# T4p0_cutout.net
KiCad netlist of a schematic drawn in EAGLE
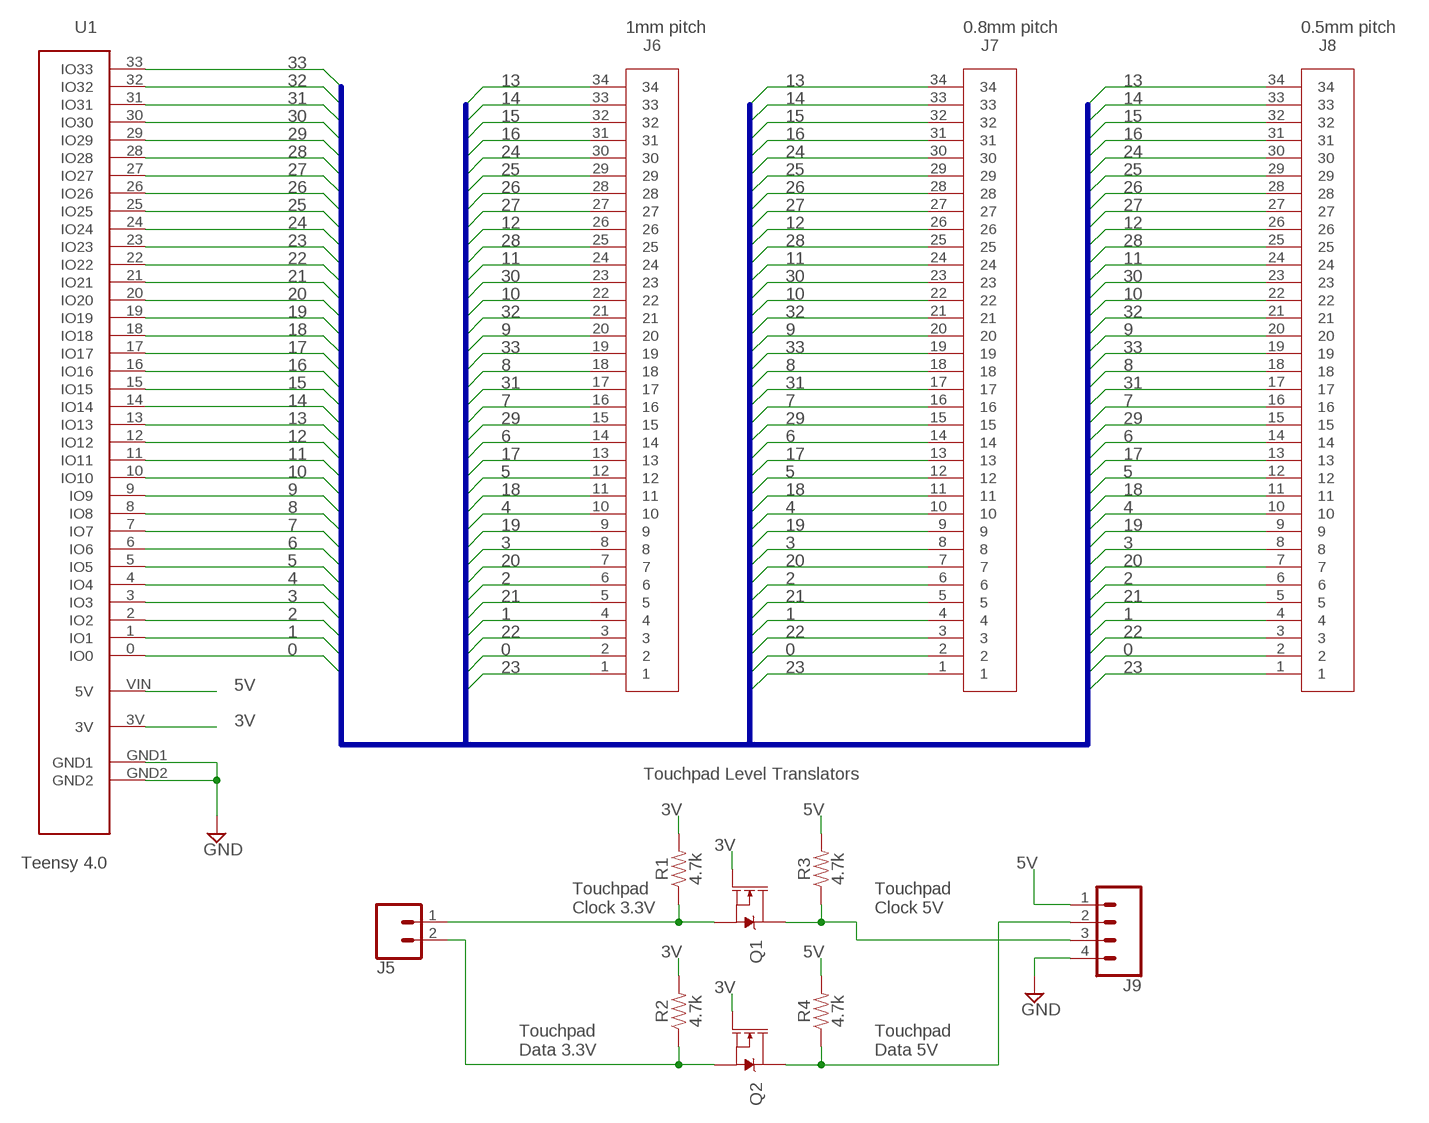
[diagram p0: schematic, sheet 1]

(export (version "E")
  (design (tool "Eeschema 10.0.6"))
  (components
    (comp (ref "J5")
      (value "CONN_021X02_NO_SILK")
      (footprint "eagle-import:1X02_NO_SILK")
      (libsource (lib "eagle-import") (part "CONN_021X02_NO_SILK"))
    )
    (comp (ref "J6")
      (value "FPC34")
      (footprint "eagle-import:FPC34")
      (libsource (lib "eagle-import") (part "FPC34"))
    )
    (comp (ref "J7")
      (value "FPC34_P8MM")
      (footprint "eagle-import:FPC34_P8MM")
      (libsource (lib "eagle-import") (part "FPC34_P8MM"))
    )
    (comp (ref "J8")
      (value "FPC34_P5MM")
      (footprint "eagle-import:FPC34_P5MM")
      (libsource (lib "eagle-import") (part "FPC34_P5MM"))
    )
    (comp (ref "J9")
      (value "CONN_041X04_NO_SILK")
      (footprint "eagle-import:1X04_NO_SILK")
      (libsource (lib "eagle-import") (part "CONN_041X04_NO_SILK"))
    )
    (comp (ref "Q1")
      (value "220mA/50V/3.5Ω")
      (footprint "eagle-import:SOT23-3")
      (libsource (lib "eagle-import") (part "MOSFET-NCH-BSS138"))
    )
    (comp (ref "Q2")
      (value "220mA/50V/3.5Ω")
      (footprint "eagle-import:SOT23-3")
      (libsource (lib "eagle-import") (part "MOSFET-NCH-BSS138"))
    )
    (comp (ref "R1")
      (value "4.7k")
      (footprint "eagle-import:0603")
      (libsource (lib "eagle-import") (part "4.7KOHM-0603-1/10W-1%"))
    )
    (comp (ref "R2")
      (value "4.7k")
      (footprint "eagle-import:0603")
      (libsource (lib "eagle-import") (part "4.7KOHM-0603-1/10W-1%"))
    )
    (comp (ref "R3")
      (value "4.7k")
      (footprint "eagle-import:0603")
      (libsource (lib "eagle-import") (part "4.7KOHM-0603-1/10W-1%"))
    )
    (comp (ref "R4")
      (value "4.7k")
      (footprint "eagle-import:0603")
      (libsource (lib "eagle-import") (part "4.7KOHM-0603-1/10W-1%"))
    )
    (comp (ref "U1")
      (value "TEENSY4P0_CUTOUT")
      (footprint "eagle-import:TEENSY4P0_CUTOUT")
      (libsource (lib "eagle-import") (part "TEENSY4P0_CUTOUT"))
    )
  )
  (nets
    (net (code "1") (name "/0") (class "Default")
      (node (ref "J6") (pin "2") (pinfunction "2_2") (pintype "bidirectional"))
      (node (ref "J7") (pin "2") (pinfunction "2_2") (pintype "bidirectional"))
      (node (ref "J8") (pin "2") (pinfunction "2_2") (pintype "bidirectional"))
      (node (ref "U1") (pin "0") (pinfunction "IO0_0") (pintype "bidirectional"))
    )
    (net (code "2") (name "/1") (class "Default")
      (node (ref "J6") (pin "4") (pinfunction "4_4") (pintype "bidirectional"))
      (node (ref "J7") (pin "4") (pinfunction "4_4") (pintype "bidirectional"))
      (node (ref "J8") (pin "4") (pinfunction "4_4") (pintype "bidirectional"))
      (node (ref "U1") (pin "1") (pinfunction "IO1_1") (pintype "bidirectional"))
    )
    (net (code "3") (name "/2") (class "Default")
      (node (ref "J6") (pin "6") (pinfunction "6_6") (pintype "bidirectional"))
      (node (ref "J7") (pin "6") (pinfunction "6_6") (pintype "bidirectional"))
      (node (ref "J8") (pin "6") (pinfunction "6_6") (pintype "bidirectional"))
      (node (ref "U1") (pin "2") (pinfunction "IO2_2") (pintype "bidirectional"))
    )
    (net (code "4") (name "/3") (class "Default")
      (node (ref "J6") (pin "8") (pinfunction "8_8") (pintype "bidirectional"))
      (node (ref "J7") (pin "8") (pinfunction "8_8") (pintype "bidirectional"))
      (node (ref "J8") (pin "8") (pinfunction "8_8") (pintype "bidirectional"))
      (node (ref "U1") (pin "3") (pinfunction "IO3_3") (pintype "bidirectional"))
    )
    (net (code "5") (name "/3V") (class "Default")
      (node (ref "Q1") (pin "1") (pinfunction "G_1") (pintype "bidirectional"))
      (node (ref "Q2") (pin "1") (pinfunction "G_1") (pintype "bidirectional"))
      (node (ref "R1") (pin "2") (pinfunction "2_2") (pintype "passive"))
      (node (ref "R2") (pin "2") (pinfunction "2_2") (pintype "passive"))
      (node (ref "U1") (pin "3V") (pinfunction "3V_3V") (pintype "bidirectional"))
    )
    (net (code "6") (name "/4") (class "Default")
      (node (ref "J6") (pin "10") (pinfunction "10_10") (pintype "bidirectional"))
      (node (ref "J7") (pin "10") (pinfunction "10_10") (pintype "bidirectional"))
      (node (ref "J8") (pin "10") (pinfunction "10_10") (pintype "bidirectional"))
      (node (ref "U1") (pin "4") (pinfunction "IO4_4") (pintype "bidirectional"))
    )
    (net (code "7") (name "/5") (class "Default")
      (node (ref "J6") (pin "12") (pinfunction "12_12") (pintype "bidirectional"))
      (node (ref "J7") (pin "12") (pinfunction "12_12") (pintype "bidirectional"))
      (node (ref "J8") (pin "12") (pinfunction "12_12") (pintype "bidirectional"))
      (node (ref "U1") (pin "5") (pinfunction "IO5_5") (pintype "bidirectional"))
    )
    (net (code "8") (name "/5V") (class "Default")
      (node (ref "J9") (pin "1") (pinfunction "1_1") (pintype "passive"))
      (node (ref "R3") (pin "2") (pinfunction "2_2") (pintype "passive"))
      (node (ref "R4") (pin "2") (pinfunction "2_2") (pintype "passive"))
      (node (ref "U1") (pin "VIN") (pinfunction "5V_VIN") (pintype "bidirectional"))
    )
    (net (code "9") (name "/6") (class "Default")
      (node (ref "J6") (pin "14") (pinfunction "14_14") (pintype "bidirectional"))
      (node (ref "J7") (pin "14") (pinfunction "14_14") (pintype "bidirectional"))
      (node (ref "J8") (pin "14") (pinfunction "14_14") (pintype "bidirectional"))
      (node (ref "U1") (pin "6") (pinfunction "IO6_6") (pintype "bidirectional"))
    )
    (net (code "10") (name "/7") (class "Default")
      (node (ref "J6") (pin "16") (pinfunction "16_16") (pintype "bidirectional"))
      (node (ref "J7") (pin "16") (pinfunction "16_16") (pintype "bidirectional"))
      (node (ref "J8") (pin "16") (pinfunction "16_16") (pintype "bidirectional"))
      (node (ref "U1") (pin "7") (pinfunction "IO7_7") (pintype "bidirectional"))
    )
    (net (code "11") (name "/8") (class "Default")
      (node (ref "J6") (pin "18") (pinfunction "18_18") (pintype "bidirectional"))
      (node (ref "J7") (pin "18") (pinfunction "18_18") (pintype "bidirectional"))
      (node (ref "J8") (pin "18") (pinfunction "18_18") (pintype "bidirectional"))
      (node (ref "U1") (pin "8") (pinfunction "IO8_8") (pintype "bidirectional"))
    )
    (net (code "12") (name "/9") (class "Default")
      (node (ref "J6") (pin "20") (pinfunction "20_20") (pintype "bidirectional"))
      (node (ref "J7") (pin "20") (pinfunction "20_20") (pintype "bidirectional"))
      (node (ref "J8") (pin "20") (pinfunction "20_20") (pintype "bidirectional"))
      (node (ref "U1") (pin "9") (pinfunction "IO9_9") (pintype "bidirectional"))
    )
    (net (code "13") (name "/10") (class "Default")
      (node (ref "J6") (pin "22") (pinfunction "22_22") (pintype "bidirectional"))
      (node (ref "J7") (pin "22") (pinfunction "22_22") (pintype "bidirectional"))
      (node (ref "J8") (pin "22") (pinfunction "22_22") (pintype "bidirectional"))
      (node (ref "U1") (pin "10") (pinfunction "IO10_10") (pintype "bidirectional"))
    )
    (net (code "14") (name "/11") (class "Default")
      (node (ref "J6") (pin "24") (pinfunction "24_24") (pintype "bidirectional"))
      (node (ref "J7") (pin "24") (pinfunction "24_24") (pintype "bidirectional"))
      (node (ref "J8") (pin "24") (pinfunction "24_24") (pintype "bidirectional"))
      (node (ref "U1") (pin "11") (pinfunction "IO11_11") (pintype "bidirectional"))
    )
    (net (code "15") (name "/12") (class "Default")
      (node (ref "J6") (pin "26") (pinfunction "26_26") (pintype "bidirectional"))
      (node (ref "J7") (pin "26") (pinfunction "26_26") (pintype "bidirectional"))
      (node (ref "J8") (pin "26") (pinfunction "26_26") (pintype "bidirectional"))
      (node (ref "U1") (pin "12") (pinfunction "IO12_12") (pintype "bidirectional"))
    )
    (net (code "16") (name "/13") (class "Default")
      (node (ref "J6") (pin "34") (pinfunction "34_34") (pintype "bidirectional"))
      (node (ref "J7") (pin "34") (pinfunction "34_34") (pintype "bidirectional"))
      (node (ref "J8") (pin "34") (pinfunction "34_34") (pintype "bidirectional"))
      (node (ref "U1") (pin "13") (pinfunction "IO13_13") (pintype "bidirectional"))
    )
    (net (code "17") (name "/14") (class "Default")
      (node (ref "J6") (pin "33") (pinfunction "33_33") (pintype "bidirectional"))
      (node (ref "J7") (pin "33") (pinfunction "33_33") (pintype "bidirectional"))
      (node (ref "J8") (pin "33") (pinfunction "33_33") (pintype "bidirectional"))
      (node (ref "U1") (pin "14") (pinfunction "IO14_14") (pintype "bidirectional"))
    )
    (net (code "18") (name "/15") (class "Default")
      (node (ref "J6") (pin "32") (pinfunction "32_32") (pintype "bidirectional"))
      (node (ref "J7") (pin "32") (pinfunction "32_32") (pintype "bidirectional"))
      (node (ref "J8") (pin "32") (pinfunction "32_32") (pintype "bidirectional"))
      (node (ref "U1") (pin "15") (pinfunction "IO15_15") (pintype "bidirectional"))
    )
    (net (code "19") (name "/16") (class "Default")
      (node (ref "J6") (pin "31") (pinfunction "31_31") (pintype "bidirectional"))
      (node (ref "J7") (pin "31") (pinfunction "31_31") (pintype "bidirectional"))
      (node (ref "J8") (pin "31") (pinfunction "31_31") (pintype "bidirectional"))
      (node (ref "U1") (pin "16") (pinfunction "IO16_16") (pintype "bidirectional"))
    )
    (net (code "20") (name "/17") (class "Default")
      (node (ref "J6") (pin "13") (pinfunction "13_13") (pintype "bidirectional"))
      (node (ref "J7") (pin "13") (pinfunction "13_13") (pintype "bidirectional"))
      (node (ref "J8") (pin "13") (pinfunction "13_13") (pintype "bidirectional"))
      (node (ref "U1") (pin "17") (pinfunction "IO17_17") (pintype "bidirectional"))
    )
    (net (code "21") (name "/18") (class "Default")
      (node (ref "J6") (pin "11") (pinfunction "11_11") (pintype "bidirectional"))
      (node (ref "J7") (pin "11") (pinfunction "11_11") (pintype "bidirectional"))
      (node (ref "J8") (pin "11") (pinfunction "11_11") (pintype "bidirectional"))
      (node (ref "U1") (pin "18") (pinfunction "IO18_18") (pintype "bidirectional"))
    )
    (net (code "22") (name "/19") (class "Default")
      (node (ref "J6") (pin "9") (pinfunction "9_9") (pintype "bidirectional"))
      (node (ref "J7") (pin "9") (pinfunction "9_9") (pintype "bidirectional"))
      (node (ref "J8") (pin "9") (pinfunction "9_9") (pintype "bidirectional"))
      (node (ref "U1") (pin "19") (pinfunction "IO19_19") (pintype "bidirectional"))
    )
    (net (code "23") (name "/20") (class "Default")
      (node (ref "J6") (pin "7") (pinfunction "7_7") (pintype "bidirectional"))
      (node (ref "J7") (pin "7") (pinfunction "7_7") (pintype "bidirectional"))
      (node (ref "J8") (pin "7") (pinfunction "7_7") (pintype "bidirectional"))
      (node (ref "U1") (pin "20") (pinfunction "IO20_20") (pintype "bidirectional"))
    )
    (net (code "24") (name "/21") (class "Default")
      (node (ref "J6") (pin "5") (pinfunction "5_5") (pintype "bidirectional"))
      (node (ref "J7") (pin "5") (pinfunction "5_5") (pintype "bidirectional"))
      (node (ref "J8") (pin "5") (pinfunction "5_5") (pintype "bidirectional"))
      (node (ref "U1") (pin "21") (pinfunction "IO21_21") (pintype "bidirectional"))
    )
    (net (code "25") (name "/22") (class "Default")
      (node (ref "J6") (pin "3") (pinfunction "3_3") (pintype "bidirectional"))
      (node (ref "J7") (pin "3") (pinfunction "3_3") (pintype "bidirectional"))
      (node (ref "J8") (pin "3") (pinfunction "3_3") (pintype "bidirectional"))
      (node (ref "U1") (pin "22") (pinfunction "IO22_22") (pintype "bidirectional"))
    )
    (net (code "26") (name "/23") (class "Default")
      (node (ref "J6") (pin "1") (pinfunction "1_1") (pintype "bidirectional"))
      (node (ref "J7") (pin "1") (pinfunction "1_1") (pintype "bidirectional"))
      (node (ref "J8") (pin "1") (pinfunction "1_1") (pintype "bidirectional"))
      (node (ref "U1") (pin "23") (pinfunction "IO23_23") (pintype "bidirectional"))
    )
    (net (code "27") (name "/24") (class "Default")
      (node (ref "J6") (pin "30") (pinfunction "30_30") (pintype "bidirectional"))
      (node (ref "J7") (pin "30") (pinfunction "30_30") (pintype "bidirectional"))
      (node (ref "J8") (pin "30") (pinfunction "30_30") (pintype "bidirectional"))
      (node (ref "U1") (pin "24") (pinfunction "IO24_24") (pintype "bidirectional"))
    )
    (net (code "28") (name "/25") (class "Default")
      (node (ref "J6") (pin "29") (pinfunction "29_29") (pintype "bidirectional"))
      (node (ref "J7") (pin "29") (pinfunction "29_29") (pintype "bidirectional"))
      (node (ref "J8") (pin "29") (pinfunction "29_29") (pintype "bidirectional"))
      (node (ref "U1") (pin "25") (pinfunction "IO25_25") (pintype "bidirectional"))
    )
    (net (code "29") (name "/26") (class "Default")
      (node (ref "J6") (pin "28") (pinfunction "28_28") (pintype "bidirectional"))
      (node (ref "J7") (pin "28") (pinfunction "28_28") (pintype "bidirectional"))
      (node (ref "J8") (pin "28") (pinfunction "28_28") (pintype "bidirectional"))
      (node (ref "U1") (pin "26") (pinfunction "IO26_26") (pintype "bidirectional"))
    )
    (net (code "30") (name "/27") (class "Default")
      (node (ref "J6") (pin "27") (pinfunction "27_27") (pintype "bidirectional"))
      (node (ref "J7") (pin "27") (pinfunction "27_27") (pintype "bidirectional"))
      (node (ref "J8") (pin "27") (pinfunction "27_27") (pintype "bidirectional"))
      (node (ref "U1") (pin "27") (pinfunction "IO27_27") (pintype "bidirectional"))
    )
    (net (code "31") (name "/28") (class "Default")
      (node (ref "J6") (pin "25") (pinfunction "25_25") (pintype "bidirectional"))
      (node (ref "J7") (pin "25") (pinfunction "25_25") (pintype "bidirectional"))
      (node (ref "J8") (pin "25") (pinfunction "25_25") (pintype "bidirectional"))
      (node (ref "U1") (pin "28") (pinfunction "IO28_28") (pintype "bidirectional"))
    )
    (net (code "32") (name "/29") (class "Default")
      (node (ref "J6") (pin "15") (pinfunction "15_15") (pintype "bidirectional"))
      (node (ref "J7") (pin "15") (pinfunction "15_15") (pintype "bidirectional"))
      (node (ref "J8") (pin "15") (pinfunction "15_15") (pintype "bidirectional"))
      (node (ref "U1") (pin "29") (pinfunction "IO29_29") (pintype "bidirectional"))
    )
    (net (code "33") (name "/30") (class "Default")
      (node (ref "J6") (pin "23") (pinfunction "23_23") (pintype "bidirectional"))
      (node (ref "J7") (pin "23") (pinfunction "23_23") (pintype "bidirectional"))
      (node (ref "J8") (pin "23") (pinfunction "23_23") (pintype "bidirectional"))
      (node (ref "U1") (pin "30") (pinfunction "IO30_30") (pintype "bidirectional"))
    )
    (net (code "34") (name "/31") (class "Default")
      (node (ref "J6") (pin "17") (pinfunction "17_17") (pintype "bidirectional"))
      (node (ref "J7") (pin "17") (pinfunction "17_17") (pintype "bidirectional"))
      (node (ref "J8") (pin "17") (pinfunction "17_17") (pintype "bidirectional"))
      (node (ref "U1") (pin "31") (pinfunction "IO31_31") (pintype "bidirectional"))
    )
    (net (code "35") (name "/32") (class "Default")
      (node (ref "J6") (pin "21") (pinfunction "21_21") (pintype "bidirectional"))
      (node (ref "J7") (pin "21") (pinfunction "21_21") (pintype "bidirectional"))
      (node (ref "J8") (pin "21") (pinfunction "21_21") (pintype "bidirectional"))
      (node (ref "U1") (pin "32") (pinfunction "IO32_32") (pintype "bidirectional"))
    )
    (net (code "36") (name "/33") (class "Default")
      (node (ref "J6") (pin "19") (pinfunction "19_19") (pintype "bidirectional"))
      (node (ref "J7") (pin "19") (pinfunction "19_19") (pintype "bidirectional"))
      (node (ref "J8") (pin "19") (pinfunction "19_19") (pintype "bidirectional"))
      (node (ref "U1") (pin "33") (pinfunction "IO33_33") (pintype "bidirectional"))
    )
    (net (code "37") (name "GND") (class "Default")
      (node (ref "J9") (pin "4") (pinfunction "4_4") (pintype "passive"))
      (node (ref "U1") (pin "GND1") (pinfunction "GND1_GND1") (pintype "bidirectional"))
      (node (ref "U1") (pin "GND2") (pinfunction "GND2_GND2") (pintype "bidirectional"))
    )
    (net (code "38") (name "Net-(Q1-D)") (class "Default")
      (node (ref "J9") (pin "3") (pinfunction "3_3") (pintype "passive"))
      (node (ref "Q1") (pin "3") (pinfunction "D_3") (pintype "bidirectional"))
      (node (ref "R3") (pin "1") (pinfunction "1_1") (pintype "passive"))
    )
    (net (code "39") (name "Net-(Q1-S)") (class "Default")
      (node (ref "J5") (pin "1") (pinfunction "1_1") (pintype "passive"))
      (node (ref "Q1") (pin "2") (pinfunction "S_2") (pintype "bidirectional"))
      (node (ref "R1") (pin "1") (pinfunction "1_1") (pintype "passive"))
    )
    (net (code "40") (name "Net-(Q2-D)") (class "Default")
      (node (ref "J9") (pin "2") (pinfunction "2_2") (pintype "passive"))
      (node (ref "Q2") (pin "3") (pinfunction "D_3") (pintype "bidirectional"))
      (node (ref "R4") (pin "1") (pinfunction "1_1") (pintype "passive"))
    )
    (net (code "41") (name "Net-(Q2-S)") (class "Default")
      (node (ref "J5") (pin "2") (pinfunction "2_2") (pintype "passive"))
      (node (ref "Q2") (pin "2") (pinfunction "S_2") (pintype "bidirectional"))
      (node (ref "R2") (pin "1") (pinfunction "1_1") (pintype "passive"))
    )
  )
)
